# semistatic.net
KiCad netlist of a schematic drawn in EAGLE
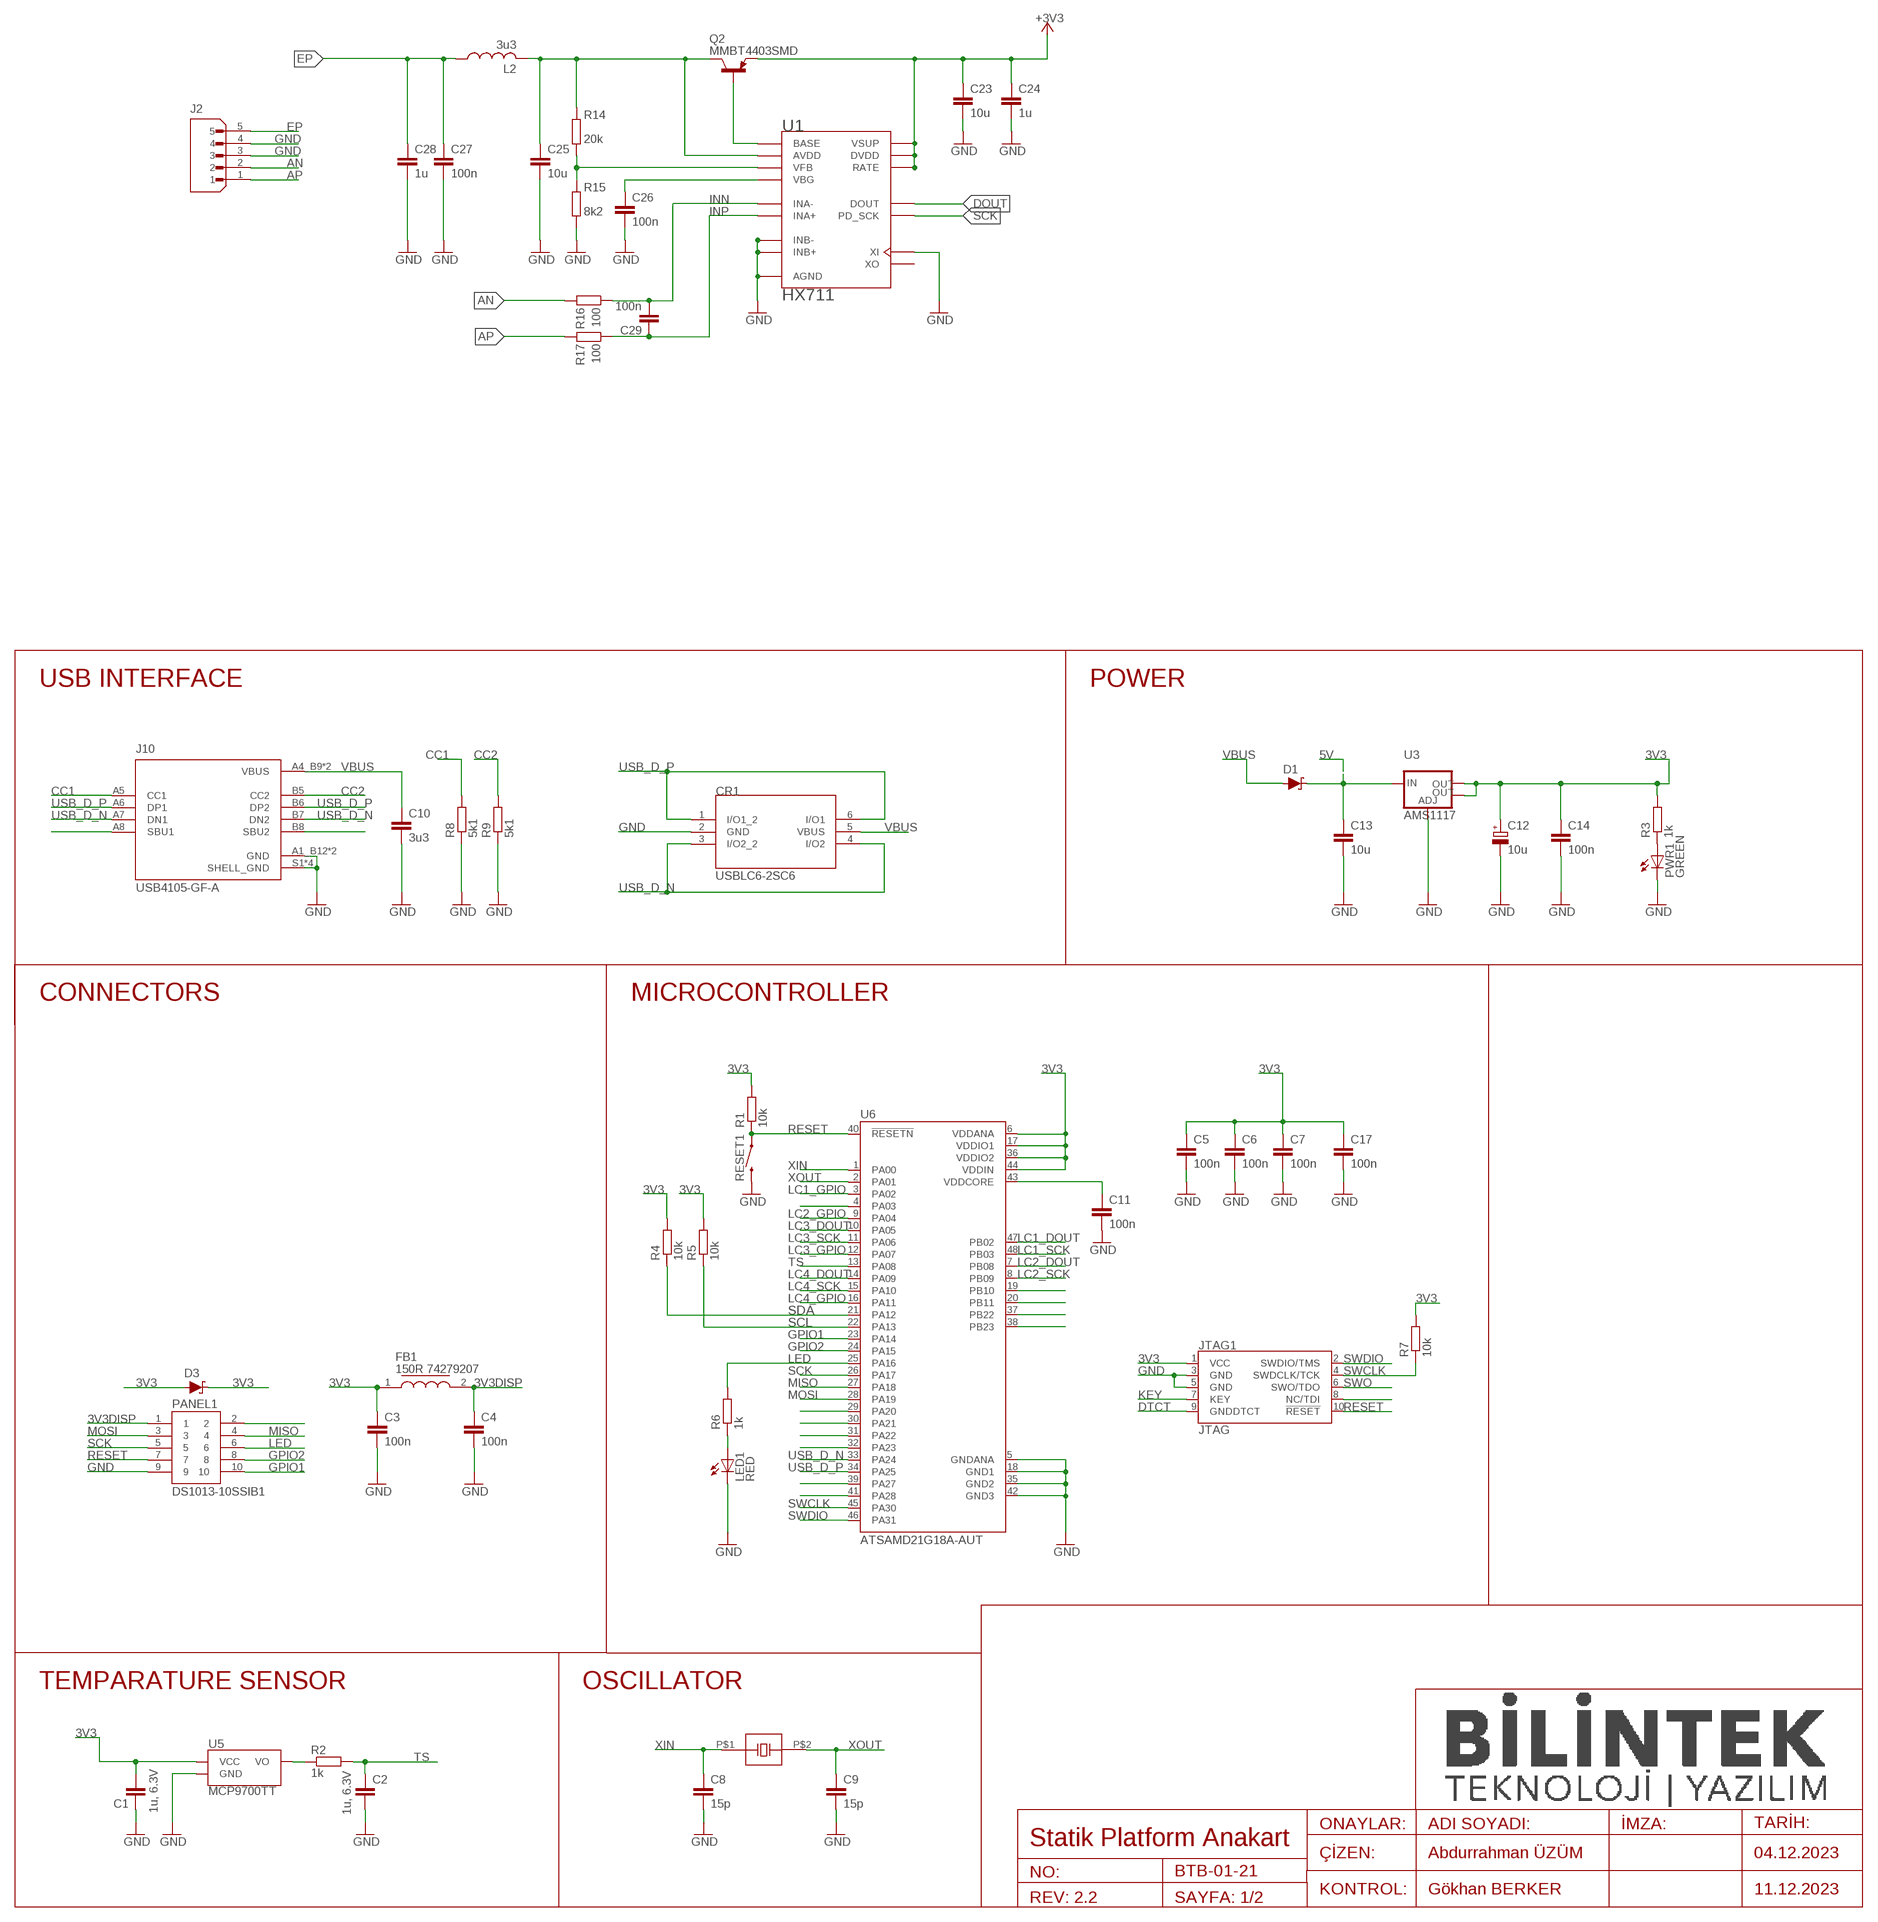
[diagram p0: schematic, sheet 1, part 1 of 2]
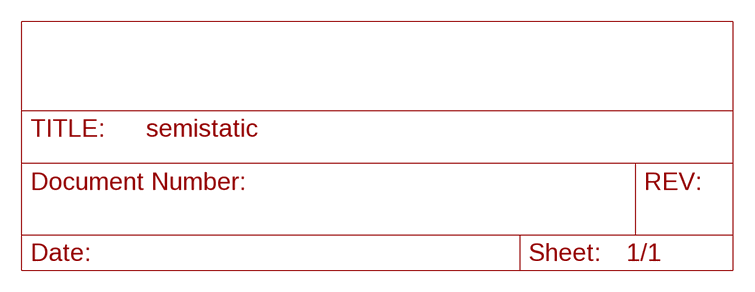
[diagram p1: schematic, sheet 1, part 2 of 2]

(export (version "E")
  (design (tool "Eeschema 10.0.6"))
  (components
    (comp (ref "C1")
      (value "1u, 6.3V")
      (footprint "eagle-import:C0603")
      (libsource (lib "eagle-import") (part "C-EUC0603"))
    )
    (comp (ref "C2")
      (value "1u, 6.3V")
      (footprint "eagle-import:C0603")
      (libsource (lib "eagle-import") (part "C-EUC0603"))
    )
    (comp (ref "C3")
      (value "100n")
      (footprint "eagle-import:C0603")
      (libsource (lib "eagle-import") (part "C-EUC0603"))
    )
    (comp (ref "C4")
      (value "100n")
      (footprint "eagle-import:C0603")
      (libsource (lib "eagle-import") (part "C-EUC0603"))
    )
    (comp (ref "C5")
      (value "100n")
      (footprint "eagle-import:C0603")
      (libsource (lib "eagle-import") (part "C-EUC0603"))
    )
    (comp (ref "C6")
      (value "100n")
      (footprint "eagle-import:C0603")
      (libsource (lib "eagle-import") (part "C-EUC0603"))
    )
    (comp (ref "C7")
      (value "100n")
      (footprint "eagle-import:C0603")
      (libsource (lib "eagle-import") (part "C-EUC0603"))
    )
    (comp (ref "C8")
      (value "15p")
      (footprint "eagle-import:C0603")
      (libsource (lib "eagle-import") (part "C-EUC0603"))
    )
    (comp (ref "C9")
      (value "15p")
      (footprint "eagle-import:C0603")
      (libsource (lib "eagle-import") (part "C-EUC0603"))
    )
    (comp (ref "C10")
      (value "3u3")
      (footprint "eagle-import:C0603K")
      (libsource (lib "eagle-import") (part "C-EUC0603K"))
    )
    (comp (ref "C11")
      (value "100n")
      (footprint "eagle-import:C0603")
      (libsource (lib "eagle-import") (part "C-EUC0603"))
    )
    (comp (ref "C12")
      (value "10u")
      (footprint "eagle-import:PANASONIC_D")
      (libsource (lib "eagle-import") (part "CPOL-EUD"))
    )
    (comp (ref "C13")
      (value "10u")
      (footprint "eagle-import:C0603")
      (libsource (lib "eagle-import") (part "C-EUC0603"))
    )
    (comp (ref "C14")
      (value "100n")
      (footprint "eagle-import:C0603")
      (libsource (lib "eagle-import") (part "C-EUC0603"))
    )
    (comp (ref "C17")
      (value "100n")
      (footprint "eagle-import:C0603")
      (libsource (lib "eagle-import") (part "C-EUC0603"))
    )
    (comp (ref "C23")
      (value "10u")
      (footprint "eagle-import:C0603")
      (libsource (lib "eagle-import") (part "C-EUC0603"))
    )
    (comp (ref "C24")
      (value "1u")
      (footprint "eagle-import:C0603")
      (libsource (lib "eagle-import") (part "C-EUC0603"))
    )
    (comp (ref "C25")
      (value "10u")
      (footprint "eagle-import:C0603")
      (libsource (lib "eagle-import") (part "C-EUC0603"))
    )
    (comp (ref "C26")
      (value "100n")
      (footprint "eagle-import:C0603")
      (libsource (lib "eagle-import") (part "C-EUC0603"))
    )
    (comp (ref "C27")
      (value "100n")
      (footprint "eagle-import:C0603")
      (libsource (lib "eagle-import") (part "C-EUC0603"))
    )
    (comp (ref "C28")
      (value "1u")
      (footprint "eagle-import:C0603")
      (libsource (lib "eagle-import") (part "C-EUC0603"))
    )
    (comp (ref "C29")
      (value "100n")
      (footprint "eagle-import:C0603")
      (libsource (lib "eagle-import") (part "C-EUC0603"))
    )
    (comp (ref "CR1")
      (value "USBLC6-2SC6")
      (footprint "eagle-import:SOT23-6L_STM")
      (fields (field (name "COPYRIGHT") "Copyright (C) 2023 Ultra Librarian. All rights reserved."))
      (libsource (lib "eagle-import") (part "USBLC6-2SC6"))
    )
    (comp (ref "D1")
      (value "3A/10V/280mV")
      (footprint "eagle-import:SOD-323")
      (libsource (lib "eagle-import") (part "DIODE-SCHOTTKY-BAT60A"))
    )
    (comp (ref "D3")
      (value "3A/10V/280mV")
      (footprint "eagle-import:SOD-323")
      (libsource (lib "eagle-import") (part "DIODE-SCHOTTKY-BAT60A"))
    )
    (comp (ref "FB1")
      (value "150R 74279207")
      (footprint "eagle-import:CAPC2012X90N")
      (fields
        (field (name "MANUFACTURER_PART_NUMBER") "74279207")
        (field (name "MOUSER_PART_NUMBER") "710-74279207")
      )
      (libsource (lib "eagle-import") (part "74279207"))
    )
    (comp (ref "J2")
      (value "B5B-XH-A(LF)(SN)")
      (footprint "eagle-import:JST_B5B-XH-A(LF)(SN)")
      (fields (field (name "MF") "JST Sales America Inc."))
      (libsource (lib "eagle-import") (part "B5B-XH-A(LF)(SN)"))
    )
    (comp (ref "J10")
      (value "USB4105-GF-A")
      (footprint "eagle-import:GCT_USB4105-GF-A")
      (fields (field (name "MF") "GCT"))
      (libsource (lib "eagle-import") (part "USB4105-GF-A"))
    )
    (comp (ref "JTAG1")
      (value "JTAG")
      (footprint "eagle-import:SAMTECH_FTSH-105-01")
      (libsource (lib "eagle-import") (part "CORTEX_DEBUG_SMD"))
    )
    (comp (ref "L2")
      (value "3u3")
      (footprint "eagle-import:L3216C")
      (libsource (lib "eagle-import") (part "L-USL3216C"))
    )
    (comp (ref "LED1")
      (value "RED")
      (footprint "eagle-import:CHIPLED_0805")
      (libsource (lib "eagle-import") (part "LEDCHIPLED_0805"))
    )
    (comp (ref "PANEL1")
      (value "DS1013-10SSIB1")
      (footprint "eagle-import:CONNFLY_DS1013-10SSIB1")
      (fields (field (name "MF") "Connfly"))
      (libsource (lib "eagle-import") (part "DS1013-10SSIB1"))
    )
    (comp (ref "PWR1")
      (value "GREEN")
      (footprint "eagle-import:CHIPLED_0805")
      (libsource (lib "eagle-import") (part "LEDCHIPLED_0805"))
    )
    (comp (ref "Q2")
      (value "MMBT4403SMD")
      (footprint "eagle-import:SOT23-BEC")
      (fields (field (name "MF") "ON Semiconductor") (field (name "MP") "MMBT4403"))
      (libsource (lib "eagle-import") (part "MMBT4403SMD"))
    )
    (comp (ref "R1")
      (value "10k")
      (footprint "eagle-import:R0603")
      (libsource (lib "eagle-import") (part "R-EU_R0603"))
    )
    (comp (ref "R2")
      (value "1k")
      (footprint "eagle-import:R0603")
      (libsource (lib "eagle-import") (part "R-EU_R0603"))
    )
    (comp (ref "R3")
      (value "1k")
      (footprint "eagle-import:R0603")
      (libsource (lib "eagle-import") (part "R-EU_R0603"))
    )
    (comp (ref "R4")
      (value "10k")
      (footprint "eagle-import:R0603")
      (libsource (lib "eagle-import") (part "R-EU_R0603"))
    )
    (comp (ref "R5")
      (value "10k")
      (footprint "eagle-import:R0603")
      (libsource (lib "eagle-import") (part "R-EU_R0603"))
    )
    (comp (ref "R6")
      (value "1k")
      (footprint "eagle-import:R0603")
      (libsource (lib "eagle-import") (part "R-EU_R0603"))
    )
    (comp (ref "R7")
      (value "10k")
      (footprint "eagle-import:R0603")
      (libsource (lib "eagle-import") (part "R-EU_R0603"))
    )
    (comp (ref "R8")
      (value "5k1")
      (footprint "eagle-import:R0603")
      (libsource (lib "eagle-import") (part "R-EU_R0603"))
    )
    (comp (ref "R9")
      (value "5k1")
      (footprint "eagle-import:R0603")
      (libsource (lib "eagle-import") (part "R-EU_R0603"))
    )
    (comp (ref "R14")
      (value "20k")
      (footprint "eagle-import:R0603")
      (libsource (lib "eagle-import") (part "R-EU_R0603"))
    )
    (comp (ref "R15")
      (value "8k2")
      (footprint "eagle-import:R0603")
      (libsource (lib "eagle-import") (part "R-EU_R0603"))
    )
    (comp (ref "R16")
      (value "100")
      (footprint "eagle-import:R0603")
      (libsource (lib "eagle-import") (part "R-EU_R0603"))
    )
    (comp (ref "R17")
      (value "100")
      (footprint "eagle-import:R0603")
      (libsource (lib "eagle-import") (part "R-EU_R0603"))
    )
    (comp (ref "RESET1")
      (value "MOMENTARY-SWITCH-SPST-SMD-6.0X3.5MM")
      (footprint "eagle-import:TACTILE_SWITCH_SMD_6.0X3.5MM")
      (libsource (lib "eagle-import") (part "MOMENTARY-SWITCH-SPST-SMD-6.0X3.5MM"))
    )
    (comp (ref "U1")
      (value "HX711")
      (footprint "eagle-import:SOP127P600X180-16N")
      (fields (field (name "MF") "AVIA SEMICONDUCTOR"))
      (libsource (lib "eagle-import") (part "HX711"))
    )
    (comp (ref "U3")
      (value "AMS1117")
      (footprint "eagle-import:SOT223")
      (libsource (lib "eagle-import") (part "V_REG_LM1117SOT223"))
    )
    (comp (ref "U5")
      (value "MCP9700TT")
      (footprint "eagle-import:SOT23-3")
      (libsource (lib "eagle-import") (part "MCP9700TT"))
    )
    (comp (ref "U6")
      (value "ATSAMD21G18A-AUT")
      (footprint "eagle-import:QFP50P900X900X120-48N")
      (fields (field (name "MF") "Microchip"))
      (libsource (lib "eagle-import") (part "ATSAMD21G18A-AUT"))
    )
    (comp (ref "Y2")
      (value "32728")
      (footprint "eagle-import:CRYSTALSAMD")
      (libsource (lib "eagle-import") (part "CRYSTALSAMD"))
    )
  )
  (nets
    (net (code "1") (name "+3V3") (class "Default")
      (node (ref "C23") (pin "1") (pinfunction "1_1") (pintype "passive"))
      (node (ref "C24") (pin "1") (pinfunction "1_1") (pintype "passive"))
      (node (ref "Q2") (pin "E") (pinfunction "E_E") (pintype "passive"))
      (node (ref "U1") (pin "1") (pinfunction "VSUP_1") (pintype "power_in"))
      (node (ref "U1") (pin "15") (pinfunction "RATE_15") (pintype "input"))
      (node (ref "U1") (pin "16") (pinfunction "DVDD_16") (pintype "power_in"))
    )
    (net (code "2") (name "/3V3") (class "Default")
      (node (ref "C1") (pin "2") (pinfunction "2_2") (pintype "passive"))
      (node (ref "C12") (pin "+") (pinfunction "+_+") (pintype "passive"))
      (node (ref "C14") (pin "1") (pinfunction "1_1") (pintype "passive"))
      (node (ref "C17") (pin "1") (pinfunction "1_1") (pintype "passive"))
      (node (ref "C3") (pin "1") (pinfunction "1_1") (pintype "passive"))
      (node (ref "C5") (pin "1") (pinfunction "1_1") (pintype "passive"))
      (node (ref "C6") (pin "1") (pinfunction "1_1") (pintype "passive"))
      (node (ref "C7") (pin "1") (pinfunction "1_1") (pintype "passive"))
      (node (ref "D3") (pin "A") (pinfunction "A_A") (pintype "passive"))
      (node (ref "D3") (pin "C") (pinfunction "C_C") (pintype "passive"))
      (node (ref "FB1") (pin "1") (pinfunction "1_1") (pintype "bidirectional"))
      (node (ref "JTAG1") (pin "1") (pinfunction "VCC_1") (pintype "bidirectional"))
      (node (ref "R1") (pin "2") (pinfunction "2_2") (pintype "passive"))
      (node (ref "R3") (pin "2") (pinfunction "2_2") (pintype "passive"))
      (node (ref "R4") (pin "2") (pinfunction "2_2") (pintype "passive"))
      (node (ref "R5") (pin "2") (pinfunction "2_2") (pintype "passive"))
      (node (ref "R7") (pin "2") (pinfunction "2_2") (pintype "passive"))
      (node (ref "U3") (pin "2") (pinfunction "OUT_2") (pintype "output"))
      (node (ref "U3") (pin "4") (pinfunction "OUT_4") (pintype "output"))
      (node (ref "U5") (pin "1") (pinfunction "VCC_1") (pintype "bidirectional"))
      (node (ref "U6") (pin "17") (pinfunction "VDDIO1_17") (pintype "power_in"))
      (node (ref "U6") (pin "36") (pinfunction "VDDIO2_36") (pintype "power_in"))
      (node (ref "U6") (pin "44") (pinfunction "VDDIN_44") (pintype "power_in"))
      (node (ref "U6") (pin "6") (pinfunction "VDDANA_6") (pintype "power_in"))
    )
    (net (code "3") (name "/3V3DISP") (class "Default")
      (node (ref "C4") (pin "1") (pinfunction "1_1") (pintype "passive"))
      (node (ref "FB1") (pin "2") (pinfunction "2_2") (pintype "bidirectional"))
      (node (ref "PANEL1") (pin "1") (pinfunction "1_1") (pintype "passive"))
    )
    (net (code "4") (name "/5V") (class "Default")
      (node (ref "C13") (pin "1") (pinfunction "1_1") (pintype "passive"))
      (node (ref "D1") (pin "C") (pinfunction "C_C") (pintype "passive"))
      (node (ref "U3") (pin "3") (pinfunction "IN_3") (pintype "input"))
    )
    (net (code "5") (name "/CC1") (class "Default")
      (node (ref "J10") (pin "A5") (pinfunction "CC1_A5") (pintype "bidirectional"))
      (node (ref "R8") (pin "2") (pinfunction "2_2") (pintype "passive"))
    )
    (net (code "6") (name "/CC2") (class "Default")
      (node (ref "J10") (pin "B5") (pinfunction "CC2_B5") (pintype "bidirectional"))
      (node (ref "R9") (pin "2") (pinfunction "2_2") (pintype "passive"))
    )
    (net (code "7") (name "/DTCT") (class "Default")
      (node (ref "JTAG1") (pin "9") (pinfunction "GNDDTCT_9") (pintype "bidirectional"))
    )
    (net (code "8") (name "/GPIO1") (class "Default")
      (node (ref "PANEL1") (pin "10") (pinfunction "10_10") (pintype "passive"))
      (node (ref "U6") (pin "23") (pinfunction "PA14_23") (pintype "bidirectional"))
    )
    (net (code "9") (name "/GPIO2") (class "Default")
      (node (ref "PANEL1") (pin "8") (pinfunction "8_8") (pintype "passive"))
      (node (ref "U6") (pin "24") (pinfunction "PA15_24") (pintype "bidirectional"))
    )
    (net (code "10") (name "/INN") (class "Default")
      (node (ref "C29") (pin "2") (pinfunction "2_2") (pintype "passive"))
      (node (ref "R16") (pin "1") (pinfunction "1_1") (pintype "passive"))
      (node (ref "U1") (pin "7") (pinfunction "INA-_7") (pintype "input"))
    )
    (net (code "11") (name "/INP") (class "Default")
      (node (ref "C29") (pin "1") (pinfunction "1_1") (pintype "passive"))
      (node (ref "R17") (pin "1") (pinfunction "1_1") (pintype "passive"))
      (node (ref "U1") (pin "8") (pinfunction "INA+_8") (pintype "input"))
    )
    (net (code "12") (name "/KEY") (class "Default")
      (node (ref "JTAG1") (pin "7") (pinfunction "KEY_7") (pintype "bidirectional"))
    )
    (net (code "13") (name "/LC1_DOUT") (class "Default")
      (node (ref "U6") (pin "47") (pinfunction "PB02_47") (pintype "bidirectional"))
    )
    (net (code "14") (name "/LC1_GPIO") (class "Default")
      (node (ref "U6") (pin "3") (pinfunction "PA02_3") (pintype "bidirectional"))
    )
    (net (code "15") (name "/LC1_SCK") (class "Default")
      (node (ref "U6") (pin "48") (pinfunction "PB03_48") (pintype "bidirectional"))
    )
    (net (code "16") (name "/LC2_DOUT") (class "Default")
      (node (ref "U6") (pin "7") (pinfunction "PB08_7") (pintype "bidirectional"))
    )
    (net (code "17") (name "/LC2_GPIO") (class "Default")
      (node (ref "U6") (pin "9") (pinfunction "PA04_9") (pintype "bidirectional"))
    )
    (net (code "18") (name "/LC2_SCK") (class "Default")
      (node (ref "U6") (pin "8") (pinfunction "PB09_8") (pintype "bidirectional"))
    )
    (net (code "19") (name "/LC3_DOUT") (class "Default")
      (node (ref "U6") (pin "10") (pinfunction "PA05_10") (pintype "bidirectional"))
    )
    (net (code "20") (name "/LC3_GPIO") (class "Default")
      (node (ref "U6") (pin "12") (pinfunction "PA07_12") (pintype "bidirectional"))
    )
    (net (code "21") (name "/LC3_SCK") (class "Default")
      (node (ref "U6") (pin "11") (pinfunction "PA06_11") (pintype "bidirectional"))
    )
    (net (code "22") (name "/LC4_DOUT") (class "Default")
      (node (ref "U6") (pin "14") (pinfunction "PA09_14") (pintype "bidirectional"))
    )
    (net (code "23") (name "/LC4_GPIO") (class "Default")
      (node (ref "U6") (pin "16") (pinfunction "PA11_16") (pintype "bidirectional"))
    )
    (net (code "24") (name "/LC4_SCK") (class "Default")
      (node (ref "U6") (pin "15") (pinfunction "PA10_15") (pintype "bidirectional"))
    )
    (net (code "25") (name "/LED") (class "Default")
      (node (ref "PANEL1") (pin "6") (pinfunction "6_6") (pintype "passive"))
      (node (ref "R6") (pin "2") (pinfunction "2_2") (pintype "passive"))
      (node (ref "U6") (pin "25") (pinfunction "PA16_25") (pintype "bidirectional"))
    )
    (net (code "26") (name "/MISO") (class "Default")
      (node (ref "PANEL1") (pin "4") (pinfunction "4_4") (pintype "passive"))
      (node (ref "U6") (pin "27") (pinfunction "PA18_27") (pintype "bidirectional"))
    )
    (net (code "27") (name "/MOSI") (class "Default")
      (node (ref "PANEL1") (pin "3") (pinfunction "3_3") (pintype "passive"))
      (node (ref "U6") (pin "28") (pinfunction "PA19_28") (pintype "bidirectional"))
    )
    (net (code "28") (name "/RESET") (class "Default")
      (node (ref "JTAG1") (pin "10") (pinfunction "~{RESET}_10") (pintype "bidirectional"))
      (node (ref "PANEL1") (pin "7") (pinfunction "7_7") (pintype "passive"))
      (node (ref "R1") (pin "1") (pinfunction "1_1") (pintype "passive"))
      (node (ref "RESET1") (pin "1") (pinfunction "1_1") (pintype "passive"))
      (node (ref "U6") (pin "40") (pinfunction "~{RESETN}_40") (pintype "input"))
    )
    (net (code "29") (name "/SCL") (class "Default")
      (node (ref "R5") (pin "1") (pinfunction "1_1") (pintype "passive"))
      (node (ref "U6") (pin "22") (pinfunction "PA13_22") (pintype "bidirectional"))
    )
    (net (code "30") (name "/SDA") (class "Default")
      (node (ref "R4") (pin "1") (pinfunction "1_1") (pintype "passive"))
      (node (ref "U6") (pin "21") (pinfunction "PA12_21") (pintype "bidirectional"))
    )
    (net (code "31") (name "/SWCLK") (class "Default")
      (node (ref "JTAG1") (pin "4") (pinfunction "SWDCLK/TCK_4") (pintype "bidirectional"))
      (node (ref "R7") (pin "1") (pinfunction "1_1") (pintype "passive"))
      (node (ref "U6") (pin "45") (pinfunction "PA30_45") (pintype "bidirectional"))
    )
    (net (code "32") (name "/SWDIO") (class "Default")
      (node (ref "JTAG1") (pin "2") (pinfunction "SWDIO/TMS_2") (pintype "bidirectional"))
      (node (ref "U6") (pin "46") (pinfunction "PA31_46") (pintype "bidirectional"))
    )
    (net (code "33") (name "/SWO") (class "Default")
      (node (ref "JTAG1") (pin "6") (pinfunction "SWO/TDO_6") (pintype "bidirectional"))
    )
    (net (code "34") (name "/TS") (class "Default")
      (node (ref "C2") (pin "1") (pinfunction "1_1") (pintype "passive"))
      (node (ref "R2") (pin "2") (pinfunction "2_2") (pintype "passive"))
      (node (ref "U6") (pin "13") (pinfunction "PA08_13") (pintype "bidirectional"))
    )
    (net (code "35") (name "/USB_D_N") (class "Default")
      (node (ref "CR1") (pin "3") (pinfunction "I/O2_2_3") (pintype "bidirectional"))
      (node (ref "CR1") (pin "4") (pinfunction "I/O2_4") (pintype "bidirectional"))
      (node (ref "J10") (pin "A7") (pinfunction "DN1_A7") (pintype "bidirectional"))
      (node (ref "J10") (pin "B7") (pinfunction "DN2_B7") (pintype "bidirectional"))
      (node (ref "U6") (pin "33") (pinfunction "PA24_33") (pintype "bidirectional"))
    )
    (net (code "36") (name "/USB_D_P") (class "Default")
      (node (ref "CR1") (pin "1") (pinfunction "I/O1_2_1") (pintype "bidirectional"))
      (node (ref "CR1") (pin "6") (pinfunction "I/O1_6") (pintype "bidirectional"))
      (node (ref "J10") (pin "A6") (pinfunction "DP1_A6") (pintype "bidirectional"))
      (node (ref "J10") (pin "B6") (pinfunction "DP2_B6") (pintype "bidirectional"))
      (node (ref "U6") (pin "34") (pinfunction "PA25_34") (pintype "bidirectional"))
    )
    (net (code "37") (name "/VBUS") (class "Default")
      (node (ref "C10") (pin "1") (pinfunction "1_1") (pintype "passive"))
      (node (ref "CR1") (pin "5") (pinfunction "VBUS_5") (pintype "power_in"))
      (node (ref "D1") (pin "A") (pinfunction "A_A") (pintype "passive"))
      (node (ref "J10") (pin "A4_B9") (pinfunction "VBUS_A4_B9") (pintype "power_in"))
      (node (ref "J10") (pin "B4_A9") (pinfunction "VBUS_B4_A9") (pintype "power_in"))
    )
    (net (code "38") (name "/XIN") (class "Default")
      (node (ref "C8") (pin "1") (pinfunction "1_1") (pintype "passive"))
      (node (ref "U6") (pin "1") (pinfunction "PA00_1") (pintype "bidirectional"))
      (node (ref "Y2") (pin "P$1") (pinfunction "XIN_P$1") (pintype "bidirectional"))
    )
    (net (code "39") (name "/XOUT") (class "Default")
      (node (ref "C9") (pin "1") (pinfunction "1_1") (pintype "passive"))
      (node (ref "U6") (pin "2") (pinfunction "PA01_2") (pintype "bidirectional"))
      (node (ref "Y2") (pin "P$2") (pinfunction "XOUT_P$2") (pintype "bidirectional"))
    )
    (net (code "40") (name "AN") (class "Default")
      (node (ref "J2") (pin "2") (pinfunction "2_2") (pintype "passive"))
      (node (ref "R16") (pin "2") (pinfunction "2_2") (pintype "passive"))
    )
    (net (code "41") (name "AP") (class "Default")
      (node (ref "J2") (pin "1") (pinfunction "1_1") (pintype "passive"))
      (node (ref "R17") (pin "2") (pinfunction "2_2") (pintype "passive"))
    )
    (net (code "42") (name "DOUT") (class "Default")
      (node (ref "U1") (pin "12") (pinfunction "DOUT_12") (pintype "output"))
    )
    (net (code "43") (name "EP") (class "Default")
      (node (ref "C27") (pin "1") (pinfunction "1_1") (pintype "passive"))
      (node (ref "C28") (pin "1") (pinfunction "1_1") (pintype "passive"))
      (node (ref "J2") (pin "5") (pinfunction "5_5") (pintype "passive"))
      (node (ref "L2") (pin "1") (pinfunction "1_1") (pintype "passive"))
    )
    (net (code "44") (name "GND") (class "Default")
      (node (ref "C1") (pin "1") (pinfunction "1_1") (pintype "passive"))
      (node (ref "C10") (pin "2") (pinfunction "2_2") (pintype "passive"))
      (node (ref "C11") (pin "2") (pinfunction "2_2") (pintype "passive"))
      (node (ref "C12") (pin "-") (pinfunction "-_-") (pintype "passive"))
      (node (ref "C13") (pin "2") (pinfunction "2_2") (pintype "passive"))
      (node (ref "C14") (pin "2") (pinfunction "2_2") (pintype "passive"))
      (node (ref "C17") (pin "2") (pinfunction "2_2") (pintype "passive"))
      (node (ref "C2") (pin "2") (pinfunction "2_2") (pintype "passive"))
      (node (ref "C23") (pin "2") (pinfunction "2_2") (pintype "passive"))
      (node (ref "C24") (pin "2") (pinfunction "2_2") (pintype "passive"))
      (node (ref "C25") (pin "2") (pinfunction "2_2") (pintype "passive"))
      (node (ref "C26") (pin "2") (pinfunction "2_2") (pintype "passive"))
      (node (ref "C27") (pin "2") (pinfunction "2_2") (pintype "passive"))
      (node (ref "C28") (pin "2") (pinfunction "2_2") (pintype "passive"))
      (node (ref "C3") (pin "2") (pinfunction "2_2") (pintype "passive"))
      (node (ref "C4") (pin "2") (pinfunction "2_2") (pintype "passive"))
      (node (ref "C5") (pin "2") (pinfunction "2_2") (pintype "passive"))
      (node (ref "C6") (pin "2") (pinfunction "2_2") (pintype "passive"))
      (node (ref "C7") (pin "2") (pinfunction "2_2") (pintype "passive"))
      (node (ref "C8") (pin "2") (pinfunction "2_2") (pintype "passive"))
      (node (ref "C9") (pin "2") (pinfunction "2_2") (pintype "passive"))
      (node (ref "CR1") (pin "2") (pinfunction "GND_2") (pintype "power_in"))
      (node (ref "J10") (pin "A1_B12") (pinfunction "GND_A1_B12") (pintype "power_in"))
      (node (ref "J10") (pin "B1_A12") (pinfunction "GND_B1_A12") (pintype "power_in"))
      (node (ref "J10") (pin "S1") (pinfunction "SHELL_GND_S1") (pintype "power_in"))
      (node (ref "J10") (pin "S2") (pinfunction "SHELL_GND_S2") (pintype "power_in"))
      (node (ref "J10") (pin "S3") (pinfunction "SHELL_GND_S3") (pintype "power_in"))
      (node (ref "J10") (pin "S4") (pinfunction "SHELL_GND_S4") (pintype "power_in"))
      (node (ref "J2") (pin "3") (pinfunction "3_3") (pintype "passive"))
      (node (ref "J2") (pin "4") (pinfunction "4_4") (pintype "passive"))
      (node (ref "JTAG1") (pin "3") (pinfunction "GND_3") (pintype "bidirectional"))
      (node (ref "JTAG1") (pin "5") (pinfunction "GND_5") (pintype "bidirectional"))
      (node (ref "LED1") (pin "C") (pinfunction "C_C") (pintype "passive"))
      (node (ref "PANEL1") (pin "9") (pinfunction "9_9") (pintype "passive"))
      (node (ref "PWR1") (pin "C") (pinfunction "C_C") (pintype "passive"))
      (node (ref "R15") (pin "2") (pinfunction "2_2") (pintype "passive"))
      (node (ref "R8") (pin "1") (pinfunction "1_1") (pintype "passive"))
      (node (ref "R9") (pin "1") (pinfunction "1_1") (pintype "passive"))
      (node (ref "RESET1") (pin "2") (pinfunction "2_2") (pintype "passive"))
      (node (ref "U1") (pin "10") (pinfunction "INB+_10") (pintype "input"))
      (node (ref "U1") (pin "14") (pinfunction "XI_14") (pintype "input"))
      (node (ref "U1") (pin "5") (pinfunction "AGND_5") (pintype "power_in"))
      (node (ref "U1") (pin "9") (pinfunction "INB-_9") (pintype "input"))
      (node (ref "U3") (pin "1") (pinfunction "ADJ_1") (pintype "input"))
      (node (ref "U5") (pin "3") (pinfunction "GND_3") (pintype "bidirectional"))
      (node (ref "U6") (pin "18") (pinfunction "GND1_18") (pintype "power_in"))
      (node (ref "U6") (pin "35") (pinfunction "GND2_35") (pintype "power_in"))
      (node (ref "U6") (pin "42") (pinfunction "GND3_42") (pintype "power_in"))
      (node (ref "U6") (pin "5") (pinfunction "GNDANA_5") (pintype "power_in"))
    )
    (net (code "45") (name "Net-(LED1-PadA)") (class "Default")
      (node (ref "LED1") (pin "A") (pinfunction "A_A") (pintype "passive"))
      (node (ref "R6") (pin "1") (pinfunction "1_1") (pintype "passive"))
    )
    (net (code "46") (name "Net-(PWR1-PadA)") (class "Default")
      (node (ref "PWR1") (pin "A") (pinfunction "A_A") (pintype "passive"))
      (node (ref "R3") (pin "1") (pinfunction "1_1") (pintype "passive"))
    )
    (net (code "47") (name "Net-(U1-AVDD)") (class "Default")
      (node (ref "C25") (pin "1") (pinfunction "1_1") (pintype "passive"))
      (node (ref "L2") (pin "2") (pinfunction "2_2") (pintype "passive"))
      (node (ref "Q2") (pin "C") (pinfunction "C_C") (pintype "passive"))
      (node (ref "R14") (pin "1") (pinfunction "1_1") (pintype "passive"))
      (node (ref "U1") (pin "3") (pinfunction "AVDD_3") (pintype "power_in"))
    )
    (net (code "48") (name "Net-(U1-BASE)") (class "Default")
      (node (ref "Q2") (pin "B") (pinfunction "B_B") (pintype "passive"))
      (node (ref "U1") (pin "2") (pinfunction "BASE_2") (pintype "output"))
    )
    (net (code "49") (name "Net-(U1-VBG)") (class "Default")
      (node (ref "C26") (pin "1") (pinfunction "1_1") (pintype "passive"))
      (node (ref "U1") (pin "6") (pinfunction "VBG_6") (pintype "output"))
    )
    (net (code "50") (name "Net-(U1-VFB)") (class "Default")
      (node (ref "R14") (pin "2") (pinfunction "2_2") (pintype "passive"))
      (node (ref "R15") (pin "1") (pinfunction "1_1") (pintype "passive"))
      (node (ref "U1") (pin "4") (pinfunction "VFB_4") (pintype "input"))
    )
    (net (code "51") (name "Net-(U5-VO)") (class "Default")
      (node (ref "R2") (pin "1") (pinfunction "1_1") (pintype "passive"))
      (node (ref "U5") (pin "2") (pinfunction "VO_2") (pintype "bidirectional"))
    )
    (net (code "52") (name "Net-(U6-VDDCORE)") (class "Default")
      (node (ref "C11") (pin "1") (pinfunction "1_1") (pintype "passive"))
      (node (ref "U6") (pin "43") (pinfunction "VDDCORE_43") (pintype "power_in"))
    )
    (net (code "53") (name "SCK") (class "Default")
      (node (ref "PANEL1") (pin "5") (pinfunction "5_5") (pintype "passive"))
      (node (ref "U1") (pin "11") (pinfunction "PD_SCK_11") (pintype "input"))
      (node (ref "U6") (pin "26") (pinfunction "PA17_26") (pintype "bidirectional"))
    )
    (net (code "54") (name "unconnected-(J10-SBU1-PadA8)") (class "Default")
      (node (ref "J10") (pin "A8") (pinfunction "SBU1_A8") (pintype "bidirectional"))
    )
    (net (code "55") (name "unconnected-(J10-SBU2-PadB8)") (class "Default")
      (node (ref "J10") (pin "B8") (pinfunction "SBU2_B8") (pintype "bidirectional"))
    )
    (net (code "56") (name "unconnected-(JTAG1-NC{slash}TDI-Pad8)") (class "Default")
      (node (ref "JTAG1") (pin "8") (pinfunction "NC/TDI_8") (pintype "bidirectional"))
    )
    (net (code "57") (name "unconnected-(PANEL1-Pad2)") (class "Default")
      (node (ref "PANEL1") (pin "2") (pinfunction "2_2") (pintype "passive"))
    )
    (net (code "58") (name "unconnected-(U1-XO-Pad13)") (class "Default")
      (node (ref "U1") (pin "13") (pinfunction "XO_13") (pintype "output"))
    )
    (net (code "59") (name "unconnected-(U6-PA03-Pad4)") (class "Default")
      (node (ref "U6") (pin "4") (pinfunction "PA03_4") (pintype "bidirectional"))
    )
    (net (code "60") (name "unconnected-(U6-PA20-Pad29)") (class "Default")
      (node (ref "U6") (pin "29") (pinfunction "PA20_29") (pintype "bidirectional"))
    )
    (net (code "61") (name "unconnected-(U6-PA21-Pad30)") (class "Default")
      (node (ref "U6") (pin "30") (pinfunction "PA21_30") (pintype "bidirectional"))
    )
    (net (code "62") (name "unconnected-(U6-PA22-Pad31)") (class "Default")
      (node (ref "U6") (pin "31") (pinfunction "PA22_31") (pintype "bidirectional"))
    )
    (net (code "63") (name "unconnected-(U6-PA23-Pad32)") (class "Default")
      (node (ref "U6") (pin "32") (pinfunction "PA23_32") (pintype "bidirectional"))
    )
    (net (code "64") (name "unconnected-(U6-PA27-Pad39)") (class "Default")
      (node (ref "U6") (pin "39") (pinfunction "PA27_39") (pintype "bidirectional"))
    )
    (net (code "65") (name "unconnected-(U6-PA28-Pad41)") (class "Default")
      (node (ref "U6") (pin "41") (pinfunction "PA28_41") (pintype "bidirectional"))
    )
    (net (code "66") (name "unconnected-(U6-PB10-Pad19)") (class "Default")
      (node (ref "U6") (pin "19") (pinfunction "PB10_19") (pintype "bidirectional"))
    )
    (net (code "67") (name "unconnected-(U6-PB11-Pad20)") (class "Default")
      (node (ref "U6") (pin "20") (pinfunction "PB11_20") (pintype "bidirectional"))
    )
    (net (code "68") (name "unconnected-(U6-PB22-Pad37)") (class "Default")
      (node (ref "U6") (pin "37") (pinfunction "PB22_37") (pintype "bidirectional"))
    )
    (net (code "69") (name "unconnected-(U6-PB23-Pad38)") (class "Default")
      (node (ref "U6") (pin "38") (pinfunction "PB23_38") (pintype "bidirectional"))
    )
  )
)
